# Airplane_Navigation___Telemetry_Schemati.net
KiCad netlist of a schematic drawn in Altium Designer
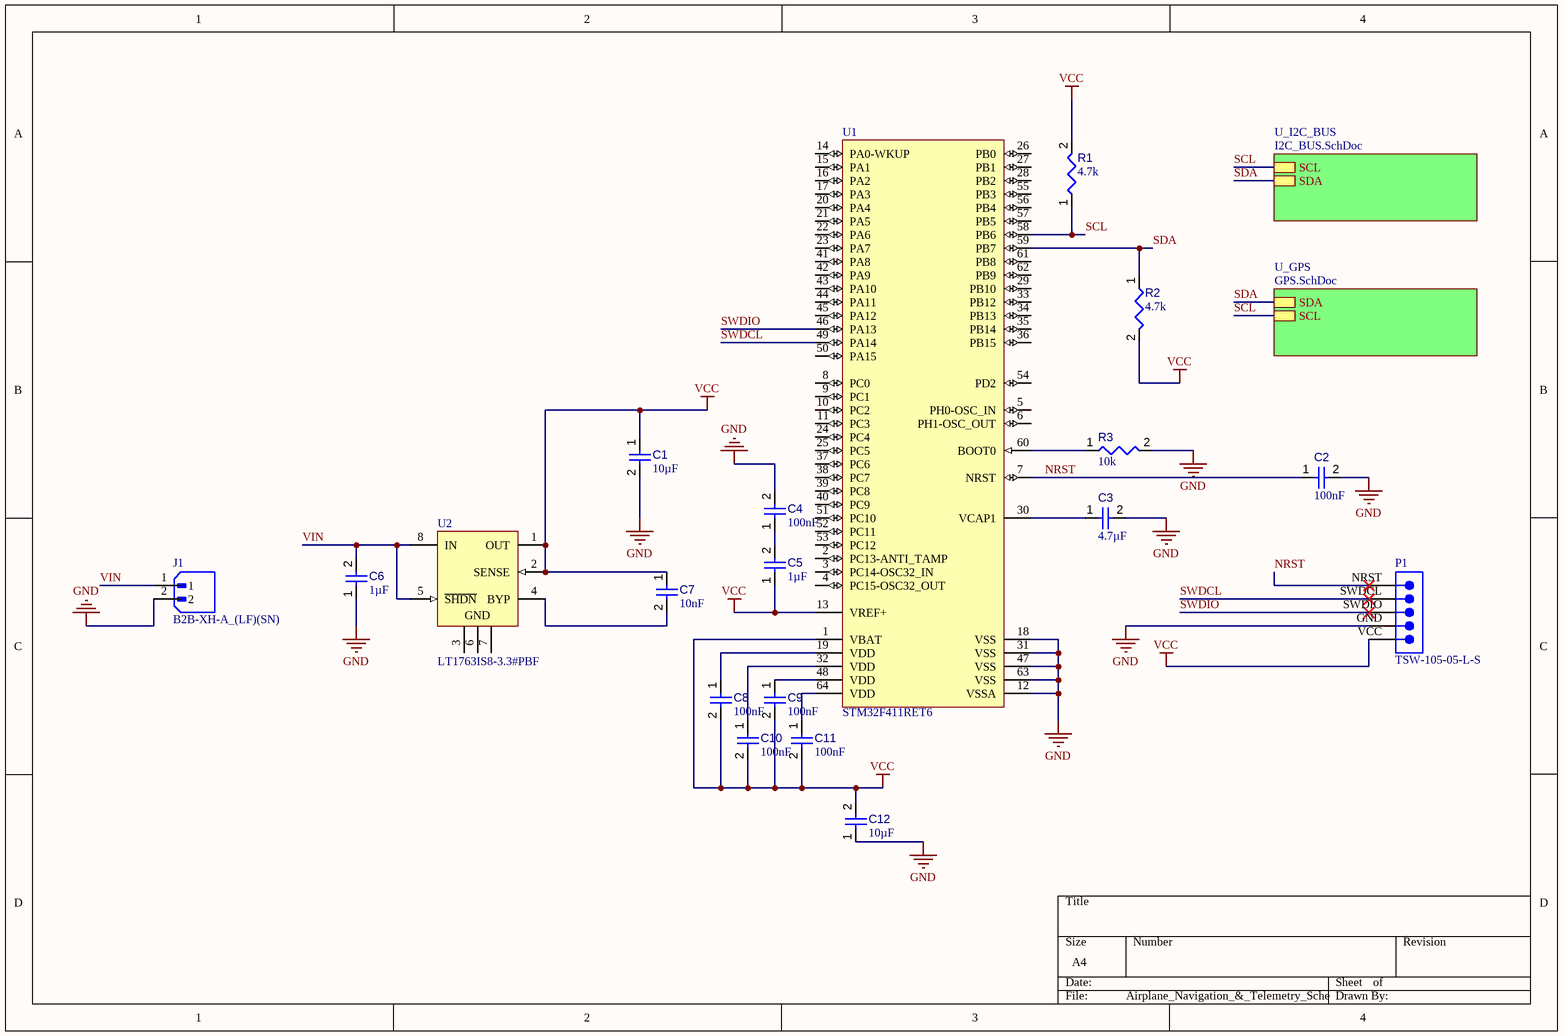
[diagram p0: Airplane_Navigation_&_Telemetry_Schematic.SchDoc]

(export (version "E")
  (design (tool "Eeschema 10.0.6"))
  (components
    (comp (ref "C1")
      (value "10µF")
      (footprint "CAPC0805(2012)145_L")
      (description "Chip Capacitor, 10µF +/-20%, 25V, 0805, Thickness 1.45 mm")
      (fields (field (name "TOLERANCE") "10%") (field (name "Comment") "Capacitor 10µF +/-20% 25V 0805"))
      (libsource (lib "Lachlan Biersteker") (part "CAP-NP-2"))
    )
    (comp (ref "C2")
      (value "100nF")
      (footprint "CAPC1608X90X40NL10T20")
      (description "Chip Capacitor, 100 nF, +/- 10%, 50 V, 0603 (1608 Metric)")
      (fields (field (name "TOLERANCE") "10%") (field (name "Comment") "Capacitor 100 nF +/-10% 50 V 0603"))
      (libsource (lib "Lachlan Biersteker") (part "CAP-NP-2"))
    )
    (comp (ref "C3")
      (value "4.7µF")
      (footprint "CAPC0603(1608)100_L")
      (description "Chip Capacitor, 4.7µF +/-20%, 10V, 0603, Thickness 1 mm")
      (fields (field (name "TOLERANCE") "10%") (field (name "Comment") "Capacitor 4.7µF +/-20% 10V 0603"))
      (libsource (lib "Lachlan Biersteker") (part "CAP-NP-2"))
    )
    (comp (ref "C4")
      (value "100nF")
      (footprint "CAPC1608X90X40NL10T20")
      (description "Chip Capacitor, 100 nF, +/- 10%, 50 V, 0603 (1608 Metric)")
      (fields (field (name "TOLERANCE") "10%") (field (name "Comment") "Capacitor 100 nF +/-10% 50 V 0603"))
      (libsource (lib "Lachlan Biersteker") (part "CAP-NP-2"))
    )
    (comp (ref "C5")
      (value "1µF")
      (footprint "CAPC1608X90X35ML15T15")
      (description "Chip Capacitor, 1 uF, +/- 10%, 16 V, 0603 (1608 Metric)")
      (fields (field (name "TOLERANCE") "10%") (field (name "Comment") "Capacitor 1uF +/- 10% 16V 0603"))
      (libsource (lib "Lachlan Biersteker") (part "CAP-NP-2"))
    )
    (comp (ref "C6")
      (value "1µF")
      (footprint "CAPC1608X90X35ML15T15")
      (description "Chip Capacitor, 1 uF, +/- 10%, 16 V, 0603 (1608 Metric)")
      (fields (field (name "TOLERANCE") "10%") (field (name "Comment") "Capacitor 1uF +/- 10% 16V 0603"))
      (libsource (lib "Lachlan Biersteker") (part "CAP-NP-2"))
    )
    (comp (ref "C7")
      (value "10nF")
      (footprint "CAPC0402(1005)60_L")
      (description "Chip Capacitor, 10nF +/-20%, 50V, 0402, Thickness 0.6 mm")
      (fields (field (name "TOLERANCE") "5%") (field (name "Comment") "Capacitor 10nF +/-20% 50V 0402"))
      (libsource (lib "Lachlan Biersteker") (part "CAP-NP-2"))
    )
    (comp (ref "C8")
      (value "100nF")
      (footprint "CAPC1608X90X40NL10T20")
      (description "Chip Capacitor, 100 nF, +/- 10%, 50 V, 0603 (1608 Metric)")
      (fields (field (name "TOLERANCE") "10%") (field (name "Comment") "Capacitor 100 nF +/-10% 50 V 0603"))
      (libsource (lib "Lachlan Biersteker") (part "CAP-NP-2"))
    )
    (comp (ref "C9")
      (value "100nF")
      (footprint "CAPC1608X90X40NL10T20")
      (description "Chip Capacitor, 100 nF, +/- 10%, 50 V, 0603 (1608 Metric)")
      (fields (field (name "TOLERANCE") "10%") (field (name "Comment") "Capacitor 100 nF +/-10% 50 V 0603"))
      (libsource (lib "Lachlan Biersteker") (part "CAP-NP-2"))
    )
    (comp (ref "C10")
      (value "100nF")
      (footprint "CAPC1608X90X40NL10T20")
      (description "Chip Capacitor, 100 nF, +/- 10%, 50 V, 0603 (1608 Metric)")
      (fields (field (name "TOLERANCE") "10%") (field (name "Comment") "Capacitor 100 nF +/-10% 50 V 0603"))
      (libsource (lib "Lachlan Biersteker") (part "CAP-NP-2"))
    )
    (comp (ref "C11")
      (value "100nF")
      (footprint "CAPC1608X90X40NL10T20")
      (description "Chip Capacitor, 100 nF, +/- 10%, 50 V, 0603 (1608 Metric)")
      (fields (field (name "TOLERANCE") "10%") (field (name "Comment") "Capacitor 100 nF +/-10% 50 V 0603"))
      (libsource (lib "Lachlan Biersteker") (part "CAP-NP-2"))
    )
    (comp (ref "C12")
      (value "10µF")
      (footprint "CAPC2013X135X45NL10T25")
      (description "Chip Capacitor, 10 uF, +/- 10%, 16 V, 0805 (2012 Metric)")
      (fields (field (name "TOLERANCE") "10%") (field (name "Comment") "Capacitor 10 uF +/- 10% 16 V 0805"))
      (libsource (lib "Lachlan Biersteker") (part "CAP-NP-2"))
    )
    (comp (ref "J1")
      (value "B2B-XH-A_(LF)(SN)")
      (footprint "JST_B2B-XH-A_(LF)(SN)")
      (description "Connector Header Through Hole 2 position 0.098 (2.50mm)")
      (fields (field (name "MP") "B2B-XH-A (LF)(SN)") (field (name "MF") "JST Sales"))
      (libsource (lib "Lachlan Biersteker") (part "B2B-XH-A_(LF)(SN)"))
    )
    (comp (ref "P1")
      (value "TSW-105-05-L-S")
      (footprint "SMTC-TSW-105-05-X-S")
      (description "0.025\" SQ Post Header, Through-hole, Vertical, -55 to 125 degC, 2.54 mm Pitch, 5-Pin, Male, RoHS")
      (fields (field (name "MANUFACTURER") "Samtec"))
      (libsource (lib "Altium Content Vault") (part "SMTC-TSW-105-05-X-S"))
    )
    (comp (ref "R1")
      (value "4.7k")
      (footprint "RESC0402(1005)_L")
      (description "Chip Resistor, 4,7 kOhms, +/-1 %, 63 mW, -55 to 155 degC, 0402")
      (fields (field (name "POWER") "63mW") (field (name "TOLERANCE") "1%"))
      (libsource (lib "Lachlan Biersteker") (part "RES-2"))
    )
    (comp (ref "R2")
      (value "4.7k")
      (footprint "RESC0402(1005)_L")
      (description "Chip Resistor, 4,7 kOhms, +/-1 %, 63 mW, -55 to 155 degC, 0402")
      (fields (field (name "POWER") "63mW") (field (name "TOLERANCE") "1%"))
      (libsource (lib "Lachlan Biersteker") (part "RES-2"))
    )
    (comp (ref "R3")
      (value "10k")
      (footprint "RESC1005X40X25ML05T05")
      (description "Chip Resistor, 10 KOhm, +/- 1%, 0.1 W, -55 to 155 degC, 0402 (1005 Metric)")
      (fields (field (name "TOLERANCE") "1%") (field (name "POWER") "100mW"))
      (libsource (lib "Lachlan Biersteker") (part "RES-2"))
    )
    (comp (ref "U1")
      (value "STM32F411RET6")
      (footprint "STM-LQFP64_L")
      (description "ARM Cortex-M4 32-bit MCU+FPU, 512 KB Flash, 128 KB RAM, 50 I/Os, 64-Pin LQFP, -40 to 85 degC, Tray")
      (libsource (lib "Altium Content Vault") (part "MC-ARM-STM32F411-LQFP64"))
    )
    (comp (ref "U2")
      (value "LT1763IS8-3.3#PBF")
      (footprint "LT-S8-8_N")
      (fields (field (name "MANUFACTURER") "Linear Technology"))
      (libsource (lib "Altium Content Vault") (part "LT-LT1763-S8-8"))
    )
  )
  (nets
    (net (code "1") (name "/NRST") (class "Default")
      (node (ref "C2") (pin "1") (pinfunction "1_1") (pintype "passive"))
      (node (ref "P1") (pin "NRST") (pinfunction "NRST_NRST") (pintype "passive"))
      (node (ref "U1") (pin "7") (pinfunction "NRST_7") (pintype "bidirectional"))
    )
    (net (code "2") (name "/SCL") (class "Default")
      (node (ref "R1") (pin "1") (pinfunction "1_1") (pintype "passive"))
      (node (ref "U1") (pin "58") (pinfunction "PB6_58") (pintype "bidirectional"))
    )
    (net (code "3") (name "/SDA") (class "Default")
      (node (ref "R2") (pin "1") (pinfunction "1_1") (pintype "passive"))
      (node (ref "U1") (pin "59") (pinfunction "PB7_59") (pintype "bidirectional"))
    )
    (net (code "4") (name "/SWDCL") (class "Default")
      (node (ref "P1") (pin "SWDCL") (pinfunction "SWDCL_SWDCL") (pintype "passive"))
      (node (ref "U1") (pin "49") (pinfunction "PA14_49") (pintype "bidirectional"))
    )
    (net (code "5") (name "/SWDIO") (class "Default")
      (node (ref "P1") (pin "SWDIO") (pinfunction "SWDIO_SWDIO") (pintype "passive"))
      (node (ref "U1") (pin "46") (pinfunction "PA13_46") (pintype "bidirectional"))
    )
    (net (code "6") (name "/VIN") (class "Default")
      (node (ref "C6") (pin "2") (pinfunction "2_2") (pintype "passive"))
      (node (ref "J1") (pin "1") (pinfunction "1_1") (pintype "passive"))
      (node (ref "U2") (pin "5") (pinfunction "~{SHDN}_5") (pintype "input"))
      (node (ref "U2") (pin "8") (pinfunction "IN_8") (pintype "power_in"))
    )
    (net (code "7") (name "GND") (class "Default")
      (node (ref "C1") (pin "2") (pinfunction "2_2") (pintype "passive"))
      (node (ref "C12") (pin "1") (pinfunction "1_1") (pintype "passive"))
      (node (ref "C2") (pin "2") (pinfunction "2_2") (pintype "passive"))
      (node (ref "C3") (pin "2") (pinfunction "2_2") (pintype "passive"))
      (node (ref "C4") (pin "2") (pinfunction "2_2") (pintype "passive"))
      (node (ref "C6") (pin "1") (pinfunction "1_1") (pintype "passive"))
      (node (ref "J1") (pin "2") (pinfunction "2_2") (pintype "passive"))
      (node (ref "P1") (pin "GND") (pinfunction "GND_GND") (pintype "passive"))
      (node (ref "R3") (pin "2") (pinfunction "2_2") (pintype "passive"))
      (node (ref "U1") (pin "12") (pinfunction "VSSA_12") (pintype "power_in"))
      (node (ref "U1") (pin "18") (pinfunction "VSS_18") (pintype "power_in"))
      (node (ref "U1") (pin "31") (pinfunction "VSS_31") (pintype "power_in"))
      (node (ref "U1") (pin "47") (pinfunction "VSS_47") (pintype "power_in"))
      (node (ref "U1") (pin "63") (pinfunction "VSS_63") (pintype "power_in"))
    )
    (net (code "8") (name "Net-(C4-Pad1)") (class "Default")
      (node (ref "C4") (pin "1") (pinfunction "1_1") (pintype "passive"))
      (node (ref "C5") (pin "2") (pinfunction "2_2") (pintype "passive"))
    )
    (net (code "9") (name "Net-(C8-Pad1)") (class "Default")
      (node (ref "C8") (pin "1") (pinfunction "1_1") (pintype "passive"))
      (node (ref "U1") (pin "19") (pinfunction "VDD_19") (pintype "power_in"))
    )
    (net (code "10") (name "Net-(C9-Pad1)") (class "Default")
      (node (ref "C9") (pin "1") (pinfunction "1_1") (pintype "passive"))
      (node (ref "U1") (pin "48") (pinfunction "VDD_48") (pintype "power_in"))
    )
    (net (code "11") (name "Net-(C10-Pad1)") (class "Default")
      (node (ref "C10") (pin "1") (pinfunction "1_1") (pintype "passive"))
      (node (ref "U1") (pin "32") (pinfunction "VDD_32") (pintype "power_in"))
    )
    (net (code "12") (name "Net-(C11-Pad1)") (class "Default")
      (node (ref "C11") (pin "1") (pinfunction "1_1") (pintype "passive"))
      (node (ref "U1") (pin "64") (pinfunction "VDD_64") (pintype "power_in"))
    )
    (net (code "13") (name "Net-(U1-BOOT0)") (class "Default")
      (node (ref "R3") (pin "1") (pinfunction "1_1") (pintype "passive"))
      (node (ref "U1") (pin "60") (pinfunction "BOOT0_60") (pintype "input"))
    )
    (net (code "14") (name "Net-(U1-VCAP1)") (class "Default")
      (node (ref "C3") (pin "1") (pinfunction "1_1") (pintype "passive"))
      (node (ref "U1") (pin "30") (pinfunction "VCAP1_30") (pintype "passive"))
    )
    (net (code "15") (name "Net-(U2-BYP)") (class "Default")
      (node (ref "C7") (pin "2") (pinfunction "2_2") (pintype "passive"))
      (node (ref "U2") (pin "4") (pinfunction "BYP_4") (pintype "passive"))
    )
    (net (code "16") (name "VCC") (class "Default")
      (node (ref "C1") (pin "1") (pinfunction "1_1") (pintype "passive"))
      (node (ref "C10") (pin "2") (pinfunction "2_2") (pintype "passive"))
      (node (ref "C11") (pin "2") (pinfunction "2_2") (pintype "passive"))
      (node (ref "C12") (pin "2") (pinfunction "2_2") (pintype "passive"))
      (node (ref "C5") (pin "1") (pinfunction "1_1") (pintype "passive"))
      (node (ref "C7") (pin "1") (pinfunction "1_1") (pintype "passive"))
      (node (ref "C8") (pin "2") (pinfunction "2_2") (pintype "passive"))
      (node (ref "C9") (pin "2") (pinfunction "2_2") (pintype "passive"))
      (node (ref "P1") (pin "VCC") (pinfunction "VCC_VCC") (pintype "passive"))
      (node (ref "R1") (pin "2") (pinfunction "2_2") (pintype "passive"))
      (node (ref "R2") (pin "2") (pinfunction "2_2") (pintype "passive"))
      (node (ref "U1") (pin "1") (pinfunction "VBAT_1") (pintype "power_in"))
      (node (ref "U1") (pin "13") (pinfunction "VREF+_13") (pintype "power_in"))
      (node (ref "U2") (pin "1") (pinfunction "OUT_1") (pintype "power_in"))
      (node (ref "U2") (pin "2") (pinfunction "SENSE_2") (pintype "input"))
    )
    (net (code "17") (name "unconnected-(U1-PA0-WKUP-Pad14)") (class "Default")
      (node (ref "U1") (pin "14") (pinfunction "PA0-WKUP_14") (pintype "bidirectional"))
    )
    (net (code "18") (name "unconnected-(U1-PA1-Pad15)") (class "Default")
      (node (ref "U1") (pin "15") (pinfunction "PA1_15") (pintype "bidirectional"))
    )
    (net (code "19") (name "unconnected-(U1-PA2-Pad16)") (class "Default")
      (node (ref "U1") (pin "16") (pinfunction "PA2_16") (pintype "bidirectional"))
    )
    (net (code "20") (name "unconnected-(U1-PA3-Pad17)") (class "Default")
      (node (ref "U1") (pin "17") (pinfunction "PA3_17") (pintype "bidirectional"))
    )
    (net (code "21") (name "unconnected-(U1-PA4-Pad20)") (class "Default")
      (node (ref "U1") (pin "20") (pinfunction "PA4_20") (pintype "bidirectional"))
    )
    (net (code "22") (name "unconnected-(U1-PA5-Pad21)") (class "Default")
      (node (ref "U1") (pin "21") (pinfunction "PA5_21") (pintype "bidirectional"))
    )
    (net (code "23") (name "unconnected-(U1-PA6-Pad22)") (class "Default")
      (node (ref "U1") (pin "22") (pinfunction "PA6_22") (pintype "bidirectional"))
    )
    (net (code "24") (name "unconnected-(U1-PA7-Pad23)") (class "Default")
      (node (ref "U1") (pin "23") (pinfunction "PA7_23") (pintype "bidirectional"))
    )
    (net (code "25") (name "unconnected-(U1-PA8-Pad41)") (class "Default")
      (node (ref "U1") (pin "41") (pinfunction "PA8_41") (pintype "bidirectional"))
    )
    (net (code "26") (name "unconnected-(U1-PA9-Pad42)") (class "Default")
      (node (ref "U1") (pin "42") (pinfunction "PA9_42") (pintype "bidirectional"))
    )
    (net (code "27") (name "unconnected-(U1-PA10-Pad43)") (class "Default")
      (node (ref "U1") (pin "43") (pinfunction "PA10_43") (pintype "bidirectional"))
    )
    (net (code "28") (name "unconnected-(U1-PA11-Pad44)") (class "Default")
      (node (ref "U1") (pin "44") (pinfunction "PA11_44") (pintype "bidirectional"))
    )
    (net (code "29") (name "unconnected-(U1-PA12-Pad45)") (class "Default")
      (node (ref "U1") (pin "45") (pinfunction "PA12_45") (pintype "bidirectional"))
    )
    (net (code "30") (name "unconnected-(U1-PA15-Pad50)") (class "Default")
      (node (ref "U1") (pin "50") (pinfunction "PA15_50") (pintype "bidirectional"))
    )
    (net (code "31") (name "unconnected-(U1-PB0-Pad26)") (class "Default")
      (node (ref "U1") (pin "26") (pinfunction "PB0_26") (pintype "bidirectional"))
    )
    (net (code "32") (name "unconnected-(U1-PB1-Pad27)") (class "Default")
      (node (ref "U1") (pin "27") (pinfunction "PB1_27") (pintype "bidirectional"))
    )
    (net (code "33") (name "unconnected-(U1-PB2-Pad28)") (class "Default")
      (node (ref "U1") (pin "28") (pinfunction "PB2_28") (pintype "bidirectional"))
    )
    (net (code "34") (name "unconnected-(U1-PB3-Pad55)") (class "Default")
      (node (ref "U1") (pin "55") (pinfunction "PB3_55") (pintype "bidirectional"))
    )
    (net (code "35") (name "unconnected-(U1-PB4-Pad56)") (class "Default")
      (node (ref "U1") (pin "56") (pinfunction "PB4_56") (pintype "bidirectional"))
    )
    (net (code "36") (name "unconnected-(U1-PB5-Pad57)") (class "Default")
      (node (ref "U1") (pin "57") (pinfunction "PB5_57") (pintype "bidirectional"))
    )
    (net (code "37") (name "unconnected-(U1-PB8-Pad61)") (class "Default")
      (node (ref "U1") (pin "61") (pinfunction "PB8_61") (pintype "bidirectional"))
    )
    (net (code "38") (name "unconnected-(U1-PB9-Pad62)") (class "Default")
      (node (ref "U1") (pin "62") (pinfunction "PB9_62") (pintype "bidirectional"))
    )
    (net (code "39") (name "unconnected-(U1-PB10-Pad29)") (class "Default")
      (node (ref "U1") (pin "29") (pinfunction "PB10_29") (pintype "bidirectional"))
    )
    (net (code "40") (name "unconnected-(U1-PB12-Pad33)") (class "Default")
      (node (ref "U1") (pin "33") (pinfunction "PB12_33") (pintype "bidirectional"))
    )
    (net (code "41") (name "unconnected-(U1-PB13-Pad34)") (class "Default")
      (node (ref "U1") (pin "34") (pinfunction "PB13_34") (pintype "bidirectional"))
    )
    (net (code "42") (name "unconnected-(U1-PB14-Pad35)") (class "Default")
      (node (ref "U1") (pin "35") (pinfunction "PB14_35") (pintype "bidirectional"))
    )
    (net (code "43") (name "unconnected-(U1-PB15-Pad36)") (class "Default")
      (node (ref "U1") (pin "36") (pinfunction "PB15_36") (pintype "bidirectional"))
    )
    (net (code "44") (name "unconnected-(U1-PC0-Pad8)") (class "Default")
      (node (ref "U1") (pin "8") (pinfunction "PC0_8") (pintype "bidirectional"))
    )
    (net (code "45") (name "unconnected-(U1-PC1-Pad9)") (class "Default")
      (node (ref "U1") (pin "9") (pinfunction "PC1_9") (pintype "bidirectional"))
    )
    (net (code "46") (name "unconnected-(U1-PC2-Pad10)") (class "Default")
      (node (ref "U1") (pin "10") (pinfunction "PC2_10") (pintype "bidirectional"))
    )
    (net (code "47") (name "unconnected-(U1-PC3-Pad11)") (class "Default")
      (node (ref "U1") (pin "11") (pinfunction "PC3_11") (pintype "bidirectional"))
    )
    (net (code "48") (name "unconnected-(U1-PC4-Pad24)") (class "Default")
      (node (ref "U1") (pin "24") (pinfunction "PC4_24") (pintype "bidirectional"))
    )
    (net (code "49") (name "unconnected-(U1-PC5-Pad25)") (class "Default")
      (node (ref "U1") (pin "25") (pinfunction "PC5_25") (pintype "bidirectional"))
    )
    (net (code "50") (name "unconnected-(U1-PC6-Pad37)") (class "Default")
      (node (ref "U1") (pin "37") (pinfunction "PC6_37") (pintype "bidirectional"))
    )
    (net (code "51") (name "unconnected-(U1-PC7-Pad38)") (class "Default")
      (node (ref "U1") (pin "38") (pinfunction "PC7_38") (pintype "bidirectional"))
    )
    (net (code "52") (name "unconnected-(U1-PC8-Pad39)") (class "Default")
      (node (ref "U1") (pin "39") (pinfunction "PC8_39") (pintype "bidirectional"))
    )
    (net (code "53") (name "unconnected-(U1-PC9-Pad40)") (class "Default")
      (node (ref "U1") (pin "40") (pinfunction "PC9_40") (pintype "bidirectional"))
    )
    (net (code "54") (name "unconnected-(U1-PC10-Pad51)") (class "Default")
      (node (ref "U1") (pin "51") (pinfunction "PC10_51") (pintype "bidirectional"))
    )
    (net (code "55") (name "unconnected-(U1-PC11-Pad52)") (class "Default")
      (node (ref "U1") (pin "52") (pinfunction "PC11_52") (pintype "bidirectional"))
    )
    (net (code "56") (name "unconnected-(U1-PC12-Pad53)") (class "Default")
      (node (ref "U1") (pin "53") (pinfunction "PC12_53") (pintype "bidirectional"))
    )
    (net (code "57") (name "unconnected-(U1-PC13-ANTI_TAMP-Pad2)") (class "Default")
      (node (ref "U1") (pin "2") (pinfunction "PC13-ANTI_TAMP_2") (pintype "bidirectional"))
    )
    (net (code "58") (name "unconnected-(U1-PC14-OSC32_IN-Pad3)") (class "Default")
      (node (ref "U1") (pin "3") (pinfunction "PC14-OSC32_IN_3") (pintype "bidirectional"))
    )
    (net (code "59") (name "unconnected-(U1-PC15-OSC32_OUT-Pad4)") (class "Default")
      (node (ref "U1") (pin "4") (pinfunction "PC15-OSC32_OUT_4") (pintype "bidirectional"))
    )
    (net (code "60") (name "unconnected-(U1-PD2-Pad54)") (class "Default")
      (node (ref "U1") (pin "54") (pinfunction "PD2_54") (pintype "bidirectional"))
    )
    (net (code "61") (name "unconnected-(U1-PH0-OSC_IN-Pad5)") (class "Default")
      (node (ref "U1") (pin "5") (pinfunction "PH0-OSC_IN_5") (pintype "bidirectional"))
    )
    (net (code "62") (name "unconnected-(U1-PH1-OSC_OUT-Pad6)") (class "Default")
      (node (ref "U1") (pin "6") (pinfunction "PH1-OSC_OUT_6") (pintype "bidirectional"))
    )
    (net (code "63") (name "unconnected-(U2-GND-Pad3)") (class "Default")
      (node (ref "U2") (pin "3") (pinfunction "GND_3") (pintype "power_in"))
    )
    (net (code "64") (name "unconnected-(U2-GND-Pad6)") (class "Default")
      (node (ref "U2") (pin "6") (pinfunction "GND_6") (pintype "power_in"))
    )
    (net (code "65") (name "unconnected-(U2-GND-Pad7)") (class "Default")
      (node (ref "U2") (pin "7") (pinfunction "GND_7") (pintype "power_in"))
    )
  )
)
